# fonte.net
KiCad netlist of a schematic drawn in EAGLE
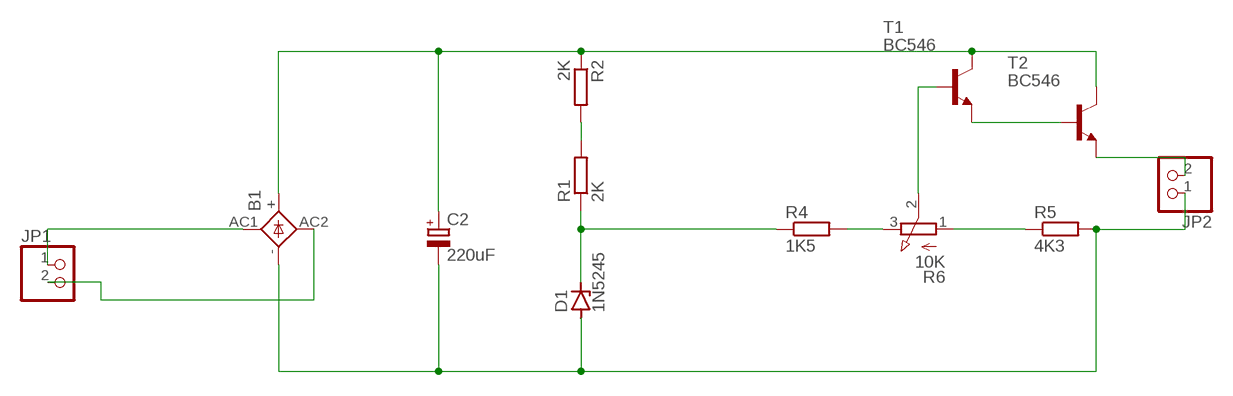
[diagram p0: schematic, sheet 1]

(export (version "E")
  (design (tool "Eeschema 10.0.6"))
  (components
    (comp (ref "B1")
      (value "KBU")
      (footprint "eagle-import:KBU")
      (libsource (lib "eagle-import") (part "KBU"))
    )
    (comp (ref "C2")
      (value "220uF")
      (footprint "eagle-import:E3,5-10")
      (libsource (lib "eagle-import") (part "CPOL-EUE3.5-10"))
    )
    (comp (ref "D1")
      (value "1N5245")
      (footprint "eagle-import:DO41Z10")
      (libsource (lib "eagle-import") (part "1N4728"))
    )
    (comp (ref "JP1")
      (value "PINHD-1X2")
      (footprint "eagle-import:1X02")
      (libsource (lib "eagle-import") (part "PINHD-1X2"))
    )
    (comp (ref "JP2")
      (value "PINHD-1X2")
      (footprint "eagle-import:1X02")
      (libsource (lib "eagle-import") (part "PINHD-1X2"))
    )
    (comp (ref "R1")
      (value "2K")
      (footprint "eagle-import:0204_7")
      (libsource (lib "eagle-import") (part "R-EU_0204/7"))
    )
    (comp (ref "R2")
      (value "2K")
      (footprint "eagle-import:0204_7")
      (libsource (lib "eagle-import") (part "R-EU_0204/7"))
    )
    (comp (ref "R4")
      (value "1K5")
      (footprint "eagle-import:0204_7")
      (libsource (lib "eagle-import") (part "R-EU_0204/7"))
    )
    (comp (ref "R5")
      (value "4K3")
      (footprint "eagle-import:0204_7")
      (libsource (lib "eagle-import") (part "R-EU_0204/7"))
    )
    (comp (ref "R6")
      (value "10K")
      (footprint "eagle-import:3RP_1610N")
      (libsource (lib "eagle-import") (part "3RP/1610N"))
    )
    (comp (ref "T1")
      (value "BC546")
      (footprint "eagle-import:TO92")
      (libsource (lib "eagle-import") (part "BC547"))
    )
    (comp (ref "T2")
      (value "BC546")
      (footprint "eagle-import:TO92")
      (libsource (lib "eagle-import") (part "BC547"))
    )
  )
  (nets
    (net (code "1") (name "Net-(B1-Pad-)") (class "Default")
      (node (ref "B1") (pin "-") (pinfunction "-_-") (pintype "passive"))
      (node (ref "C2") (pin "-") (pinfunction "-_-") (pintype "passive"))
      (node (ref "D1") (pin "A") (pinfunction "A_A") (pintype "passive"))
      (node (ref "JP2") (pin "1") (pinfunction "1_1") (pintype "passive"))
      (node (ref "R5") (pin "2") (pinfunction "2_2") (pintype "passive"))
    )
    (net (code "2") (name "Net-(B1-PadAC1)") (class "Default")
      (node (ref "B1") (pin "AC1") (pinfunction "AC1_AC1") (pintype "passive"))
      (node (ref "JP1") (pin "1") (pinfunction "1_1") (pintype "passive"))
    )
    (net (code "3") (name "Net-(B1-PadAC2)") (class "Default")
      (node (ref "B1") (pin "AC2") (pinfunction "AC2_AC2") (pintype "passive"))
      (node (ref "JP1") (pin "2") (pinfunction "2_2") (pintype "passive"))
    )
    (net (code "4") (name "Net-(D1-PadC)") (class "Default")
      (node (ref "D1") (pin "C") (pinfunction "C_C") (pintype "passive"))
      (node (ref "R1") (pin "1") (pinfunction "1_1") (pintype "passive"))
      (node (ref "R4") (pin "1") (pinfunction "1_1") (pintype "passive"))
    )
    (net (code "5") (name "Net-(R1-Pad2)") (class "Default")
      (node (ref "R1") (pin "2") (pinfunction "2_2") (pintype "passive"))
      (node (ref "R2") (pin "2") (pinfunction "2_2") (pintype "passive"))
    )
    (net (code "6") (name "Net-(R6-A)") (class "Default")
      (node (ref "R5") (pin "1") (pinfunction "1_1") (pintype "passive"))
      (node (ref "R6") (pin "1") (pinfunction "A_1") (pintype "passive"))
    )
    (net (code "7") (name "Net-(R6-E)") (class "Default")
      (node (ref "R4") (pin "2") (pinfunction "2_2") (pintype "passive"))
      (node (ref "R6") (pin "3") (pinfunction "E_3") (pintype "passive"))
    )
    (net (code "8") (name "Net-(R6-S)") (class "Default")
      (node (ref "R6") (pin "2") (pinfunction "S_2") (pintype "passive"))
      (node (ref "T1") (pin "2") (pinfunction "B_2") (pintype "passive"))
    )
    (net (code "9") (name "Net-(T1-C)") (class "Default")
      (node (ref "B1") (pin "+") (pinfunction "+_+") (pintype "passive"))
      (node (ref "C2") (pin "+") (pinfunction "+_+") (pintype "passive"))
      (node (ref "R2") (pin "1") (pinfunction "1_1") (pintype "passive"))
      (node (ref "T1") (pin "3") (pinfunction "C_3") (pintype "passive"))
      (node (ref "T2") (pin "3") (pinfunction "C_3") (pintype "passive"))
    )
    (net (code "10") (name "Net-(T1-E)") (class "Default")
      (node (ref "T1") (pin "1") (pinfunction "E_1") (pintype "passive"))
      (node (ref "T2") (pin "2") (pinfunction "B_2") (pintype "passive"))
    )
    (net (code "11") (name "Net-(T2-E)") (class "Default")
      (node (ref "JP2") (pin "2") (pinfunction "2_2") (pintype "passive"))
      (node (ref "T2") (pin "1") (pinfunction "E_1") (pintype "passive"))
    )
  )
)
